# PROB_S7CAS_FPGA_1.net
KiCad netlist of a schematic drawn in Altium Designer
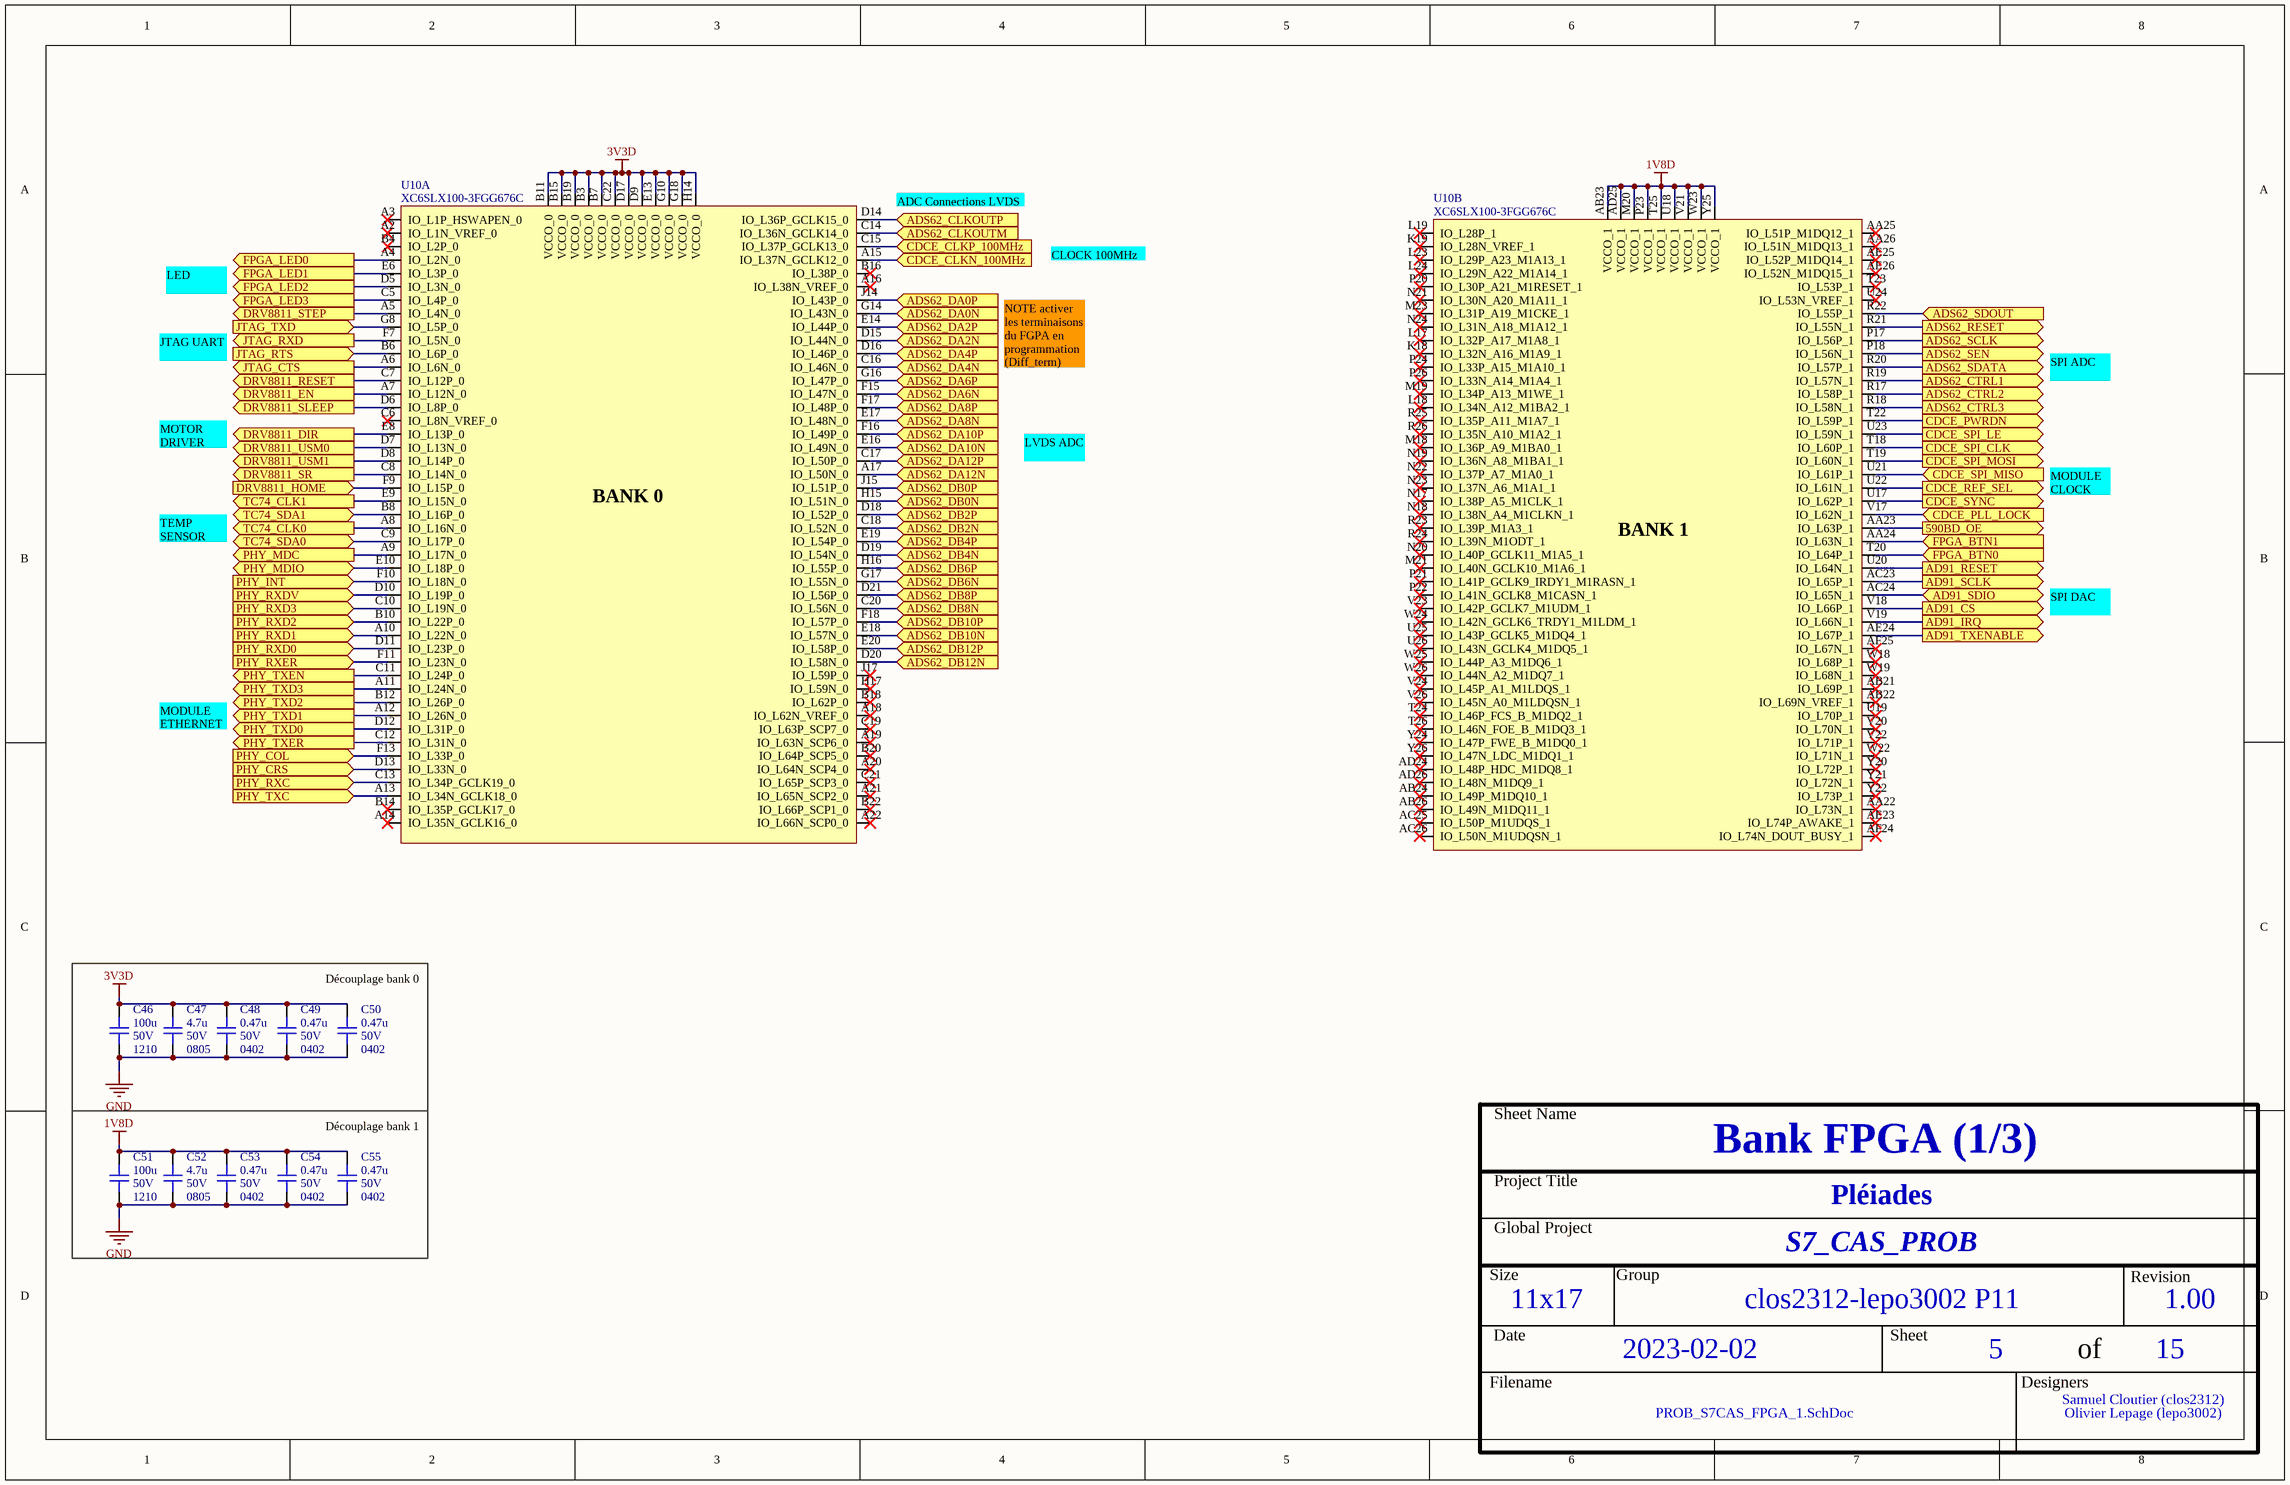
[diagram p0: PROB_S7CAS_FPGA_1.SchDoc]

(export (version "E")
  (design (tool "Eeschema 10.0.6"))
  (components
    (comp (ref "C46")
      (value "100u")
      (footprint "CAP_1210")
      (description "CAP - 1210")
      (fields
        (field (name "VOLTAGE") "50V")
        (field (name "PACKAGE") "1210")
        (field (name "CREATEDBY") "Jonathan Bouchard")
      )
      (libsource (lib "S7CAS_LIB2021") (part "CAP - 1210"))
    )
    (comp (ref "C47")
      (value "4.7u")
      (footprint "CAP_0805")
      (description "CAP - 0805")
      (fields
        (field (name "VOLTAGE") "50V")
        (field (name "PACKAGE") "0805")
        (field (name "CREATEDBY") "Jonathan Bouchard")
      )
      (libsource (lib "S7CAS_LIB2021") (part "CAP - 0805"))
    )
    (comp (ref "C48")
      (value "0.47u")
      (footprint "CAP_0402")
      (description "CAP - 0402")
      (fields
        (field (name "VOLTAGE") "50V")
        (field (name "PACKAGE") "0402")
        (field (name "CREATEDBY") "Jonathan Bouchard")
      )
      (libsource (lib "S7CAS_LIB2021") (part "CAP - 0402"))
    )
    (comp (ref "C49")
      (value "0.47u")
      (footprint "CAP_0402")
      (description "CAP - 0402")
      (fields
        (field (name "VOLTAGE") "50V")
        (field (name "PACKAGE") "0402")
        (field (name "CREATEDBY") "Jonathan Bouchard")
      )
      (libsource (lib "S7CAS_LIB2021") (part "CAP - 0402"))
    )
    (comp (ref "C50")
      (value "0.47u")
      (footprint "CAP_0402")
      (description "CAP - 0402")
      (fields
        (field (name "VOLTAGE") "50V")
        (field (name "PACKAGE") "0402")
        (field (name "CREATEDBY") "Jonathan Bouchard")
      )
      (libsource (lib "S7CAS_LIB2021") (part "CAP - 0402"))
    )
    (comp (ref "C51")
      (value "100u")
      (footprint "CAP_1210")
      (description "CAP - 1210")
      (fields
        (field (name "VOLTAGE") "50V")
        (field (name "PACKAGE") "1210")
        (field (name "CREATEDBY") "Jonathan Bouchard")
      )
      (libsource (lib "S7CAS_LIB2021") (part "CAP - 1210"))
    )
    (comp (ref "C52")
      (value "4.7u")
      (footprint "CAP_0805")
      (description "CAP - 0805")
      (fields
        (field (name "VOLTAGE") "50V")
        (field (name "PACKAGE") "0805")
        (field (name "CREATEDBY") "Jonathan Bouchard")
      )
      (libsource (lib "S7CAS_LIB2021") (part "CAP - 0805"))
    )
    (comp (ref "C53")
      (value "0.47u")
      (footprint "CAP_0402")
      (description "CAP - 0402")
      (fields
        (field (name "VOLTAGE") "50V")
        (field (name "PACKAGE") "0402")
        (field (name "CREATEDBY") "Jonathan Bouchard")
      )
      (libsource (lib "S7CAS_LIB2021") (part "CAP - 0402"))
    )
    (comp (ref "C54")
      (value "0.47u")
      (footprint "CAP_0402")
      (description "CAP - 0402")
      (fields
        (field (name "VOLTAGE") "50V")
        (field (name "PACKAGE") "0402")
        (field (name "CREATEDBY") "Jonathan Bouchard")
      )
      (libsource (lib "S7CAS_LIB2021") (part "CAP - 0402"))
    )
    (comp (ref "C55")
      (value "0.47u")
      (footprint "CAP_0402")
      (description "CAP - 0402")
      (fields
        (field (name "VOLTAGE") "50V")
        (field (name "PACKAGE") "0402")
        (field (name "CREATEDBY") "Jonathan Bouchard")
      )
      (libsource (lib "S7CAS_LIB2021") (part "CAP - 0402"))
    )
    (comp (ref "U10")
      (value "XC6SLX100-3FGG676C")
      (footprint "FPGA_XILINX_FGG676")
      (description "FPGA - XILINX SPARTAN 6 480 I/O - BGA-676")
      (fields
        (field (name "VOLTAGE") "1.14 V ~ 1.26 V")
        (field (name "MFG") "Xilinx")
        (field (name "CREATEDBY") "Jonathan Bouchard")
      )
      (libsource (lib "S7CAS_LIB2021") (part "FPGA_XC6SLX100-3FGG676C"))
    )
  )
  (nets
    (net (code "1") (name "/590BD_OE") (class "Default")
      (node (ref "U10") (pin "AA23") (pinfunction "IO_L63P_1_AA23") (pintype "passive"))
    )
    (net (code "2") (name "/AD91_CS") (class "Default")
      (node (ref "U10") (pin "V18") (pinfunction "IO_L66P_1_V18") (pintype "passive"))
    )
    (net (code "3") (name "/AD91_IRQ") (class "Default")
      (node (ref "U10") (pin "V19") (pinfunction "IO_L66N_1_V19") (pintype "passive"))
    )
    (net (code "4") (name "/AD91_RESET") (class "Default")
      (node (ref "U10") (pin "U20") (pinfunction "IO_L64N_1_U20") (pintype "passive"))
    )
    (net (code "5") (name "/AD91_SCLK") (class "Default")
      (node (ref "U10") (pin "AC23") (pinfunction "IO_L65P_1_AC23") (pintype "passive"))
    )
    (net (code "6") (name "/AD91_SDIO") (class "Default")
      (node (ref "U10") (pin "AC24") (pinfunction "IO_L65N_1_AC24") (pintype "passive"))
    )
    (net (code "7") (name "/AD91_TXENABLE") (class "Default")
      (node (ref "U10") (pin "AE24") (pinfunction "IO_L67P_1_AE24") (pintype "passive"))
    )
    (net (code "8") (name "/ADS62_CLKOUTM") (class "Default")
      (node (ref "U10") (pin "C14") (pinfunction "IO_L36N_GCLK14_0_C14") (pintype "passive"))
    )
    (net (code "9") (name "/ADS62_CLKOUTP") (class "Default")
      (node (ref "U10") (pin "D14") (pinfunction "IO_L36P_GCLK15_0_D14") (pintype "passive"))
    )
    (net (code "10") (name "/ADS62_CTRL1") (class "Default")
      (node (ref "U10") (pin "R19") (pinfunction "IO_L57N_1_R19") (pintype "passive"))
    )
    (net (code "11") (name "/ADS62_CTRL2") (class "Default")
      (node (ref "U10") (pin "R17") (pinfunction "IO_L58P_1_R17") (pintype "passive"))
    )
    (net (code "12") (name "/ADS62_CTRL3") (class "Default")
      (node (ref "U10") (pin "R18") (pinfunction "IO_L58N_1_R18") (pintype "passive"))
    )
    (net (code "13") (name "/ADS62_DA0N") (class "Default")
      (node (ref "U10") (pin "G14") (pinfunction "IO_L43N_0_G14") (pintype "passive"))
    )
    (net (code "14") (name "/ADS62_DA0P") (class "Default")
      (node (ref "U10") (pin "J14") (pinfunction "IO_L43P_0_J14") (pintype "passive"))
    )
    (net (code "15") (name "/ADS62_DA2N") (class "Default")
      (node (ref "U10") (pin "D15") (pinfunction "IO_L44N_0_D15") (pintype "passive"))
    )
    (net (code "16") (name "/ADS62_DA2P") (class "Default")
      (node (ref "U10") (pin "E14") (pinfunction "IO_L44P_0_E14") (pintype "passive"))
    )
    (net (code "17") (name "/ADS62_DA4N") (class "Default")
      (node (ref "U10") (pin "C16") (pinfunction "IO_L46N_0_C16") (pintype "passive"))
    )
    (net (code "18") (name "/ADS62_DA4P") (class "Default")
      (node (ref "U10") (pin "D16") (pinfunction "IO_L46P_0_D16") (pintype "passive"))
    )
    (net (code "19") (name "/ADS62_DA6N") (class "Default")
      (node (ref "U10") (pin "F15") (pinfunction "IO_L47N_0_F15") (pintype "passive"))
    )
    (net (code "20") (name "/ADS62_DA6P") (class "Default")
      (node (ref "U10") (pin "G16") (pinfunction "IO_L47P_0_G16") (pintype "passive"))
    )
    (net (code "21") (name "/ADS62_DA8N") (class "Default")
      (node (ref "U10") (pin "E17") (pinfunction "IO_L48N_0_E17") (pintype "passive"))
    )
    (net (code "22") (name "/ADS62_DA8P") (class "Default")
      (node (ref "U10") (pin "F17") (pinfunction "IO_L48P_0_F17") (pintype "passive"))
    )
    (net (code "23") (name "/ADS62_DA10N") (class "Default")
      (node (ref "U10") (pin "E16") (pinfunction "IO_L49N_0_E16") (pintype "passive"))
    )
    (net (code "24") (name "/ADS62_DA10P") (class "Default")
      (node (ref "U10") (pin "F16") (pinfunction "IO_L49P_0_F16") (pintype "passive"))
    )
    (net (code "25") (name "/ADS62_DA12N") (class "Default")
      (node (ref "U10") (pin "A17") (pinfunction "IO_L50N_0_A17") (pintype "passive"))
    )
    (net (code "26") (name "/ADS62_DA12P") (class "Default")
      (node (ref "U10") (pin "C17") (pinfunction "IO_L50P_0_C17") (pintype "passive"))
    )
    (net (code "27") (name "/ADS62_DB0N") (class "Default")
      (node (ref "U10") (pin "H15") (pinfunction "IO_L51N_0_H15") (pintype "passive"))
    )
    (net (code "28") (name "/ADS62_DB0P") (class "Default")
      (node (ref "U10") (pin "J15") (pinfunction "IO_L51P_0_J15") (pintype "passive"))
    )
    (net (code "29") (name "/ADS62_DB2N") (class "Default")
      (node (ref "U10") (pin "C18") (pinfunction "IO_L52N_0_C18") (pintype "passive"))
    )
    (net (code "30") (name "/ADS62_DB2P") (class "Default")
      (node (ref "U10") (pin "D18") (pinfunction "IO_L52P_0_D18") (pintype "passive"))
    )
    (net (code "31") (name "/ADS62_DB4N") (class "Default")
      (node (ref "U10") (pin "D19") (pinfunction "IO_L54N_0_D19") (pintype "passive"))
    )
    (net (code "32") (name "/ADS62_DB4P") (class "Default")
      (node (ref "U10") (pin "E19") (pinfunction "IO_L54P_0_E19") (pintype "passive"))
    )
    (net (code "33") (name "/ADS62_DB6N") (class "Default")
      (node (ref "U10") (pin "G17") (pinfunction "IO_L55N_0_G17") (pintype "passive"))
    )
    (net (code "34") (name "/ADS62_DB6P") (class "Default")
      (node (ref "U10") (pin "H16") (pinfunction "IO_L55P_0_H16") (pintype "passive"))
    )
    (net (code "35") (name "/ADS62_DB8N") (class "Default")
      (node (ref "U10") (pin "C20") (pinfunction "IO_L56N_0_C20") (pintype "passive"))
    )
    (net (code "36") (name "/ADS62_DB8P") (class "Default")
      (node (ref "U10") (pin "D21") (pinfunction "IO_L56P_0_D21") (pintype "passive"))
    )
    (net (code "37") (name "/ADS62_DB10N") (class "Default")
      (node (ref "U10") (pin "E18") (pinfunction "IO_L57N_0_E18") (pintype "passive"))
    )
    (net (code "38") (name "/ADS62_DB10P") (class "Default")
      (node (ref "U10") (pin "F18") (pinfunction "IO_L57P_0_F18") (pintype "passive"))
    )
    (net (code "39") (name "/ADS62_DB12N") (class "Default")
      (node (ref "U10") (pin "D20") (pinfunction "IO_L58N_0_D20") (pintype "passive"))
    )
    (net (code "40") (name "/ADS62_DB12P") (class "Default")
      (node (ref "U10") (pin "E20") (pinfunction "IO_L58P_0_E20") (pintype "passive"))
    )
    (net (code "41") (name "/ADS62_RESET") (class "Default")
      (node (ref "U10") (pin "R21") (pinfunction "IO_L55N_1_R21") (pintype "passive"))
    )
    (net (code "42") (name "/ADS62_SCLK") (class "Default")
      (node (ref "U10") (pin "P17") (pinfunction "IO_L56P_1_P17") (pintype "passive"))
    )
    (net (code "43") (name "/ADS62_SDATA") (class "Default")
      (node (ref "U10") (pin "R20") (pinfunction "IO_L57P_1_R20") (pintype "passive"))
    )
    (net (code "44") (name "/ADS62_SDOUT") (class "Default")
      (node (ref "U10") (pin "R22") (pinfunction "IO_L55P_1_R22") (pintype "passive"))
    )
    (net (code "45") (name "/ADS62_SEN") (class "Default")
      (node (ref "U10") (pin "P18") (pinfunction "IO_L56N_1_P18") (pintype "passive"))
    )
    (net (code "46") (name "/CDCE_CLKN_100MHz") (class "Default")
      (node (ref "U10") (pin "A15") (pinfunction "IO_L37N_GCLK12_0_A15") (pintype "passive"))
    )
    (net (code "47") (name "/CDCE_CLKP_100MHz") (class "Default")
      (node (ref "U10") (pin "C15") (pinfunction "IO_L37P_GCLK13_0_C15") (pintype "passive"))
    )
    (net (code "48") (name "/CDCE_PLL_LOCK") (class "Default")
      (node (ref "U10") (pin "V17") (pinfunction "IO_L62N_1_V17") (pintype "passive"))
    )
    (net (code "49") (name "/CDCE_PWRDN") (class "Default")
      (node (ref "U10") (pin "T22") (pinfunction "IO_L59P_1_T22") (pintype "passive"))
    )
    (net (code "50") (name "/CDCE_REF_SEL") (class "Default")
      (node (ref "U10") (pin "U22") (pinfunction "IO_L61N_1_U22") (pintype "passive"))
    )
    (net (code "51") (name "/CDCE_SPI_CLK") (class "Default")
      (node (ref "U10") (pin "T18") (pinfunction "IO_L60P_1_T18") (pintype "passive"))
    )
    (net (code "52") (name "/CDCE_SPI_LE") (class "Default")
      (node (ref "U10") (pin "U23") (pinfunction "IO_L59N_1_U23") (pintype "passive"))
    )
    (net (code "53") (name "/CDCE_SPI_MISO") (class "Default")
      (node (ref "U10") (pin "U21") (pinfunction "IO_L61P_1_U21") (pintype "passive"))
    )
    (net (code "54") (name "/CDCE_SPI_MOSI") (class "Default")
      (node (ref "U10") (pin "T19") (pinfunction "IO_L60N_1_T19") (pintype "passive"))
    )
    (net (code "55") (name "/CDCE_SYNC") (class "Default")
      (node (ref "U10") (pin "U17") (pinfunction "IO_L62P_1_U17") (pintype "passive"))
    )
    (net (code "56") (name "/DRV8811_DIR") (class "Default")
      (node (ref "U10") (pin "E8") (pinfunction "IO_L13P_0_E8") (pintype "passive"))
    )
    (net (code "57") (name "/DRV8811_EN") (class "Default")
      (node (ref "U10") (pin "A7") (pinfunction "IO_L12N_0_A7") (pintype "passive"))
    )
    (net (code "58") (name "/DRV8811_HOME") (class "Default")
      (node (ref "U10") (pin "F9") (pinfunction "IO_L15P_0_F9") (pintype "passive"))
    )
    (net (code "59") (name "/DRV8811_RESET") (class "Default")
      (node (ref "U10") (pin "C7") (pinfunction "IO_L12P_0_C7") (pintype "passive"))
    )
    (net (code "60") (name "/DRV8811_SLEEP") (class "Default")
      (node (ref "U10") (pin "D6") (pinfunction "IO_L8P_0_D6") (pintype "passive"))
    )
    (net (code "61") (name "/DRV8811_SR") (class "Default")
      (node (ref "U10") (pin "C8") (pinfunction "IO_L14N_0_C8") (pintype "passive"))
    )
    (net (code "62") (name "/DRV8811_STEP") (class "Default")
      (node (ref "U10") (pin "A5") (pinfunction "IO_L4N_0_A5") (pintype "passive"))
    )
    (net (code "63") (name "/DRV8811_USM0") (class "Default")
      (node (ref "U10") (pin "D7") (pinfunction "IO_L13N_0_D7") (pintype "passive"))
    )
    (net (code "64") (name "/DRV8811_USM1") (class "Default")
      (node (ref "U10") (pin "D8") (pinfunction "IO_L14P_0_D8") (pintype "passive"))
    )
    (net (code "65") (name "/FPGA_BTN0") (class "Default")
      (node (ref "U10") (pin "T20") (pinfunction "IO_L64P_1_T20") (pintype "passive"))
    )
    (net (code "66") (name "/FPGA_BTN1") (class "Default")
      (node (ref "U10") (pin "AA24") (pinfunction "IO_L63N_1_AA24") (pintype "passive"))
    )
    (net (code "67") (name "/FPGA_LED0") (class "Default")
      (node (ref "U10") (pin "A4") (pinfunction "IO_L2N_0_A4") (pintype "passive"))
    )
    (net (code "68") (name "/FPGA_LED1") (class "Default")
      (node (ref "U10") (pin "E6") (pinfunction "IO_L3P_0_E6") (pintype "passive"))
    )
    (net (code "69") (name "/FPGA_LED2") (class "Default")
      (node (ref "U10") (pin "D5") (pinfunction "IO_L3N_0_D5") (pintype "passive"))
    )
    (net (code "70") (name "/FPGA_LED3") (class "Default")
      (node (ref "U10") (pin "C5") (pinfunction "IO_L4P_0_C5") (pintype "passive"))
    )
    (net (code "71") (name "/JTAG_CTS") (class "Default")
      (node (ref "U10") (pin "A6") (pinfunction "IO_L6N_0_A6") (pintype "passive"))
    )
    (net (code "72") (name "/JTAG_RTS") (class "Default")
      (node (ref "U10") (pin "B6") (pinfunction "IO_L6P_0_B6") (pintype "passive"))
    )
    (net (code "73") (name "/JTAG_RXD") (class "Default")
      (node (ref "U10") (pin "F7") (pinfunction "IO_L5N_0_F7") (pintype "passive"))
    )
    (net (code "74") (name "/JTAG_TXD") (class "Default")
      (node (ref "U10") (pin "G8") (pinfunction "IO_L5P_0_G8") (pintype "passive"))
    )
    (net (code "75") (name "/PHY_COL") (class "Default")
      (node (ref "U10") (pin "F13") (pinfunction "IO_L33P_0_F13") (pintype "passive"))
    )
    (net (code "76") (name "/PHY_CRS") (class "Default")
      (node (ref "U10") (pin "D13") (pinfunction "IO_L33N_0_D13") (pintype "passive"))
    )
    (net (code "77") (name "/PHY_INT") (class "Default")
      (node (ref "U10") (pin "F10") (pinfunction "IO_L18N_0_F10") (pintype "passive"))
    )
    (net (code "78") (name "/PHY_MDC") (class "Default")
      (node (ref "U10") (pin "A9") (pinfunction "IO_L17N_0_A9") (pintype "passive"))
    )
    (net (code "79") (name "/PHY_MDIO") (class "Default")
      (node (ref "U10") (pin "E10") (pinfunction "IO_L18P_0_E10") (pintype "passive"))
    )
    (net (code "80") (name "/PHY_RXC") (class "Default")
      (node (ref "U10") (pin "C13") (pinfunction "IO_L34P_GCLK19_0_C13") (pintype "passive"))
    )
    (net (code "81") (name "/PHY_RXD0") (class "Default")
      (node (ref "U10") (pin "D11") (pinfunction "IO_L23P_0_D11") (pintype "passive"))
    )
    (net (code "82") (name "/PHY_RXD1") (class "Default")
      (node (ref "U10") (pin "A10") (pinfunction "IO_L22N_0_A10") (pintype "passive"))
    )
    (net (code "83") (name "/PHY_RXD2") (class "Default")
      (node (ref "U10") (pin "B10") (pinfunction "IO_L22P_0_B10") (pintype "passive"))
    )
    (net (code "84") (name "/PHY_RXD3") (class "Default")
      (node (ref "U10") (pin "C10") (pinfunction "IO_L19N_0_C10") (pintype "passive"))
    )
    (net (code "85") (name "/PHY_RXDV") (class "Default")
      (node (ref "U10") (pin "D10") (pinfunction "IO_L19P_0_D10") (pintype "passive"))
    )
    (net (code "86") (name "/PHY_RXER") (class "Default")
      (node (ref "U10") (pin "F11") (pinfunction "IO_L23N_0_F11") (pintype "passive"))
    )
    (net (code "87") (name "/PHY_TXC") (class "Default")
      (node (ref "U10") (pin "A13") (pinfunction "IO_L34N_GCLK18_0_A13") (pintype "passive"))
    )
    (net (code "88") (name "/PHY_TXD0") (class "Default")
      (node (ref "U10") (pin "D12") (pinfunction "IO_L31P_0_D12") (pintype "passive"))
    )
    (net (code "89") (name "/PHY_TXD1") (class "Default")
      (node (ref "U10") (pin "A12") (pinfunction "IO_L26N_0_A12") (pintype "passive"))
    )
    (net (code "90") (name "/PHY_TXD2") (class "Default")
      (node (ref "U10") (pin "B12") (pinfunction "IO_L26P_0_B12") (pintype "passive"))
    )
    (net (code "91") (name "/PHY_TXD3") (class "Default")
      (node (ref "U10") (pin "A11") (pinfunction "IO_L24N_0_A11") (pintype "passive"))
    )
    (net (code "92") (name "/PHY_TXEN") (class "Default")
      (node (ref "U10") (pin "C11") (pinfunction "IO_L24P_0_C11") (pintype "passive"))
    )
    (net (code "93") (name "/PHY_TXER") (class "Default")
      (node (ref "U10") (pin "C12") (pinfunction "IO_L31N_0_C12") (pintype "passive"))
    )
    (net (code "94") (name "/TC74_CLK0") (class "Default")
      (node (ref "U10") (pin "A8") (pinfunction "IO_L16N_0_A8") (pintype "passive"))
    )
    (net (code "95") (name "/TC74_CLK1") (class "Default")
      (node (ref "U10") (pin "E9") (pinfunction "IO_L15N_0_E9") (pintype "passive"))
    )
    (net (code "96") (name "/TC74_SDA0") (class "Default")
      (node (ref "U10") (pin "C9") (pinfunction "IO_L17P_0_C9") (pintype "passive"))
    )
    (net (code "97") (name "/TC74_SDA1") (class "Default")
      (node (ref "U10") (pin "B8") (pinfunction "IO_L16P_0_B8") (pintype "passive"))
    )
    (net (code "98") (name "1V8D") (class "Default")
      (node (ref "C51") (pin "2") (pinfunction "2_2") (pintype "passive"))
      (node (ref "C52") (pin "2") (pinfunction "2_2") (pintype "passive"))
      (node (ref "C53") (pin "2") (pinfunction "2_2") (pintype "passive"))
      (node (ref "C54") (pin "2") (pinfunction "2_2") (pintype "passive"))
      (node (ref "C55") (pin "2") (pinfunction "2_2") (pintype "passive"))
      (node (ref "U10") (pin "AB23") (pinfunction "VCCO_1_AB23") (pintype "passive"))
      (node (ref "U10") (pin "AD25") (pinfunction "VCCO_1_AD25") (pintype "passive"))
      (node (ref "U10") (pin "M20") (pinfunction "VCCO_1_M20") (pintype "passive"))
      (node (ref "U10") (pin "P23") (pinfunction "VCCO_1_P23") (pintype "passive"))
      (node (ref "U10") (pin "T25") (pinfunction "VCCO_1_T25") (pintype "passive"))
      (node (ref "U10") (pin "U18") (pinfunction "VCCO_1_U18") (pintype "passive"))
      (node (ref "U10") (pin "V21") (pinfunction "VCCO_1_V21") (pintype "passive"))
      (node (ref "U10") (pin "W23") (pinfunction "VCCO_1_W23") (pintype "passive"))
      (node (ref "U10") (pin "Y25") (pinfunction "VCCO_1_Y25") (pintype "passive"))
    )
    (net (code "99") (name "3V3D") (class "Default")
      (node (ref "C46") (pin "2") (pinfunction "2_2") (pintype "passive"))
      (node (ref "C47") (pin "2") (pinfunction "2_2") (pintype "passive"))
      (node (ref "C48") (pin "2") (pinfunction "2_2") (pintype "passive"))
      (node (ref "C49") (pin "2") (pinfunction "2_2") (pintype "passive"))
      (node (ref "C50") (pin "2") (pinfunction "2_2") (pintype "passive"))
      (node (ref "U10") (pin "B11") (pinfunction "VCCO_0_B11") (pintype "passive"))
      (node (ref "U10") (pin "B15") (pinfunction "VCCO_0_B15") (pintype "passive"))
      (node (ref "U10") (pin "B19") (pinfunction "VCCO_0_B19") (pintype "passive"))
      (node (ref "U10") (pin "B3") (pinfunction "VCCO_0_B3") (pintype "passive"))
      (node (ref "U10") (pin "B7") (pinfunction "VCCO_0_B7") (pintype "passive"))
      (node (ref "U10") (pin "C22") (pinfunction "VCCO_0_C22") (pintype "passive"))
      (node (ref "U10") (pin "D17") (pinfunction "VCCO_0_D17") (pintype "passive"))
      (node (ref "U10") (pin "D9") (pinfunction "VCCO_0_D9") (pintype "passive"))
      (node (ref "U10") (pin "E13") (pinfunction "VCCO_0_E13") (pintype "passive"))
      (node (ref "U10") (pin "G10") (pinfunction "VCCO_0_G10") (pintype "passive"))
      (node (ref "U10") (pin "G18") (pinfunction "VCCO_0_G18") (pintype "passive"))
      (node (ref "U10") (pin "H14") (pinfunction "VCCO_0_H14") (pintype "passive"))
    )
    (net (code "100") (name "GND") (class "Default")
      (node (ref "C46") (pin "1") (pinfunction "1_1") (pintype "passive"))
      (node (ref "C47") (pin "1") (pinfunction "1_1") (pintype "passive"))
      (node (ref "C48") (pin "1") (pinfunction "1_1") (pintype "passive"))
      (node (ref "C49") (pin "1") (pinfunction "1_1") (pintype "passive"))
      (node (ref "C50") (pin "1") (pinfunction "1_1") (pintype "passive"))
      (node (ref "C51") (pin "1") (pinfunction "1_1") (pintype "passive"))
      (node (ref "C52") (pin "1") (pinfunction "1_1") (pintype "passive"))
      (node (ref "C53") (pin "1") (pinfunction "1_1") (pintype "passive"))
      (node (ref "C54") (pin "1") (pinfunction "1_1") (pintype "passive"))
      (node (ref "C55") (pin "1") (pinfunction "1_1") (pintype "passive"))
    )
    (net (code "101") (name "unconnected-(U10A-IO_L1N_VREF_0-PadA2)") (class "Default")
      (node (ref "U10") (pin "A2") (pinfunction "IO_L1N_VREF_0_A2") (pintype "passive+no_connect"))
    )
    (net (code "102") (name "unconnected-(U10A-IO_L1P_HSWAPEN_0-PadA3)") (class "Default")
      (node (ref "U10") (pin "A3") (pinfunction "IO_L1P_HSWAPEN_0_A3") (pintype "passive+no_connect"))
    )
    (net (code "103") (name "unconnected-(U10A-IO_L2P_0-PadB4)") (class "Default")
      (node (ref "U10") (pin "B4") (pinfunction "IO_L2P_0_B4") (pintype "passive+no_connect"))
    )
    (net (code "104") (name "unconnected-(U10A-IO_L8N_VREF_0-PadC6)") (class "Default")
      (node (ref "U10") (pin "C6") (pinfunction "IO_L8N_VREF_0_C6") (pintype "passive+no_connect"))
    )
    (net (code "105") (name "unconnected-(U10A-IO_L35N_GCLK16_0-PadA14)") (class "Default")
      (node (ref "U10") (pin "A14") (pinfunction "IO_L35N_GCLK16_0_A14") (pintype "passive+no_connect"))
    )
    (net (code "106") (name "unconnected-(U10A-IO_L35P_GCLK17_0-PadB14)") (class "Default")
      (node (ref "U10") (pin "B14") (pinfunction "IO_L35P_GCLK17_0_B14") (pintype "passive+no_connect"))
    )
    (net (code "107") (name "unconnected-(U10A-IO_L38N_VREF_0-PadA16)") (class "Default")
      (node (ref "U10") (pin "A16") (pinfunction "IO_L38N_VREF_0_A16") (pintype "passive+no_connect"))
    )
    (net (code "108") (name "unconnected-(U10A-IO_L38P_0-PadB16)") (class "Default")
      (node (ref "U10") (pin "B16") (pinfunction "IO_L38P_0_B16") (pintype "passive+no_connect"))
    )
    (net (code "109") (name "unconnected-(U10A-IO_L59N_0-PadH17)") (class "Default")
      (node (ref "U10") (pin "H17") (pinfunction "IO_L59N_0_H17") (pintype "passive+no_connect"))
    )
    (net (code "110") (name "unconnected-(U10A-IO_L59P_0-PadJ17)") (class "Default")
      (node (ref "U10") (pin "J17") (pinfunction "IO_L59P_0_J17") (pintype "passive+no_connect"))
    )
    (net (code "111") (name "unconnected-(U10A-IO_L62N_VREF_0-PadA18)") (class "Default")
      (node (ref "U10") (pin "A18") (pinfunction "IO_L62N_VREF_0_A18") (pintype "passive+no_connect"))
    )
    (net (code "112") (name "unconnected-(U10A-IO_L62P_0-PadB18)") (class "Default")
      (node (ref "U10") (pin "B18") (pinfunction "IO_L62P_0_B18") (pintype "passive+no_connect"))
    )
    (net (code "113") (name "unconnected-(U10A-IO_L63N_SCP6_0-PadA19)") (class "Default")
      (node (ref "U10") (pin "A19") (pinfunction "IO_L63N_SCP6_0_A19") (pintype "passive+no_connect"))
    )
    (net (code "114") (name "unconnected-(U10A-IO_L63P_SCP7_0-PadC19)") (class "Default")
      (node (ref "U10") (pin "C19") (pinfunction "IO_L63P_SCP7_0_C19") (pintype "passive+no_connect"))
    )
    (net (code "115") (name "unconnected-(U10A-IO_L64N_SCP4_0-PadA20)") (class "Default")
      (node (ref "U10") (pin "A20") (pinfunction "IO_L64N_SCP4_0_A20") (pintype "passive+no_connect"))
    )
    (net (code "116") (name "unconnected-(U10A-IO_L64P_SCP5_0-PadB20)") (class "Default")
      (node (ref "U10") (pin "B20") (pinfunction "IO_L64P_SCP5_0_B20") (pintype "passive+no_connect"))
    )
    (net (code "117") (name "unconnected-(U10A-IO_L65N_SCP2_0-PadA21)") (class "Default")
      (node (ref "U10") (pin "A21") (pinfunction "IO_L65N_SCP2_0_A21") (pintype "passive+no_connect"))
    )
    (net (code "118") (name "unconnected-(U10A-IO_L65P_SCP3_0-PadC21)") (class "Default")
      (node (ref "U10") (pin "C21") (pinfunction "IO_L65P_SCP3_0_C21") (pintype "passive+no_connect"))
    )
    (net (code "119") (name "unconnected-(U10A-IO_L66N_SCP0_0-PadA22)") (class "Default")
      (node (ref "U10") (pin "A22") (pinfunction "IO_L66N_SCP0_0_A22") (pintype "passive+no_connect"))
    )
    (net (code "120") (name "unconnected-(U10A-IO_L66P_SCP1_0-PadB22)") (class "Default")
      (node (ref "U10") (pin "B22") (pinfunction "IO_L66P_SCP1_0_B22") (pintype "passive+no_connect"))
    )
    (net (code "121") (name "unconnected-(U10B-IO_L28N_VREF_1-PadK19)") (class "Default")
      (node (ref "U10") (pin "K19") (pinfunction "IO_L28N_VREF_1_K19") (pintype "passive+no_connect"))
    )
    (net (code "122") (name "unconnected-(U10B-IO_L28P_1-PadL19)") (class "Default")
      (node (ref "U10") (pin "L19") (pinfunction "IO_L28P_1_L19") (pintype "passive+no_connect"))
    )
    (net (code "123") (name "unconnected-(U10B-IO_L29N_A22_M1A14_1-PadL24)") (class "Default")
      (node (ref "U10") (pin "L24") (pinfunction "IO_L29N_A22_M1A14_1_L24") (pintype "passive+no_connect"))
    )
    (net (code "124") (name "unconnected-(U10B-IO_L29P_A23_M1A13_1-PadL23)") (class "Default")
      (node (ref "U10") (pin "L23") (pinfunction "IO_L29P_A23_M1A13_1_L23") (pintype "passive+no_connect"))
    )
    (net (code "125") (name "unconnected-(U10B-IO_L30N_A20_M1A11_1-PadN21)") (class "Default")
      (node (ref "U10") (pin "N21") (pinfunction "IO_L30N_A20_M1A11_1_N21") (pintype "passive+no_connect"))
    )
    (net (code "126") (name "unconnected-(U10B-IO_L30P_A21_M1RESET_1-PadP20)") (class "Default")
      (node (ref "U10") (pin "P20") (pinfunction "IO_L30P_A21_M1RESET_1_P20") (pintype "passive+no_connect"))
    )
    (net (code "127") (name "unconnected-(U10B-IO_L31N_A18_M1A12_1-PadN24)") (class "Default")
      (node (ref "U10") (pin "N24") (pinfunction "IO_L31N_A18_M1A12_1_N24") (pintype "passive+no_connect"))
    )
    (net (code "128") (name "unconnected-(U10B-IO_L31P_A19_M1CKE_1-PadM23)") (class "Default")
      (node (ref "U10") (pin "M23") (pinfunction "IO_L31P_A19_M1CKE_1_M23") (pintype "passive+no_connect"))
    )
    (net (code "129") (name "unconnected-(U10B-IO_L32N_A16_M1A9_1-PadK18)") (class "Default")
      (node (ref "U10") (pin "K18") (pinfunction "IO_L32N_A16_M1A9_1_K18") (pintype "passive+no_connect"))
    )
    (net (code "130") (name "unconnected-(U10B-IO_L32P_A17_M1A8_1-PadL17)") (class "Default")
      (node (ref "U10") (pin "L17") (pinfunction "IO_L32P_A17_M1A8_1_L17") (pintype "passive+no_connect"))
    )
    (net (code "131") (name "unconnected-(U10B-IO_L33N_A14_M1A4_1-PadP26)") (class "Default")
      (node (ref "U10") (pin "P26") (pinfunction "IO_L33N_A14_M1A4_1_P26") (pintype "passive+no_connect"))
    )
    (net (code "132") (name "unconnected-(U10B-IO_L33P_A15_M1A10_1-PadP24)") (class "Default")
      (node (ref "U10") (pin "P24") (pinfunction "IO_L33P_A15_M1A10_1_P24") (pintype "passive+no_connect"))
    )
    (net (code "133") (name "unconnected-(U10B-IO_L34N_A12_M1BA2_1-PadL18)") (class "Default")
      (node (ref "U10") (pin "L18") (pinfunction "IO_L34N_A12_M1BA2_1_L18") (pintype "passive+no_connect"))
    )
    (net (code "134") (name "unconnected-(U10B-IO_L34P_A13_M1WE_1-PadM19)") (class "Default")
      (node (ref "U10") (pin "M19") (pinfunction "IO_L34P_A13_M1WE_1_M19") (pintype "passive+no_connect"))
    )
    (net (code "135") (name "unconnected-(U10B-IO_L35N_A10_M1A2_1-PadR26)") (class "Default")
      (node (ref "U10") (pin "R26") (pinfunction "IO_L35N_A10_M1A2_1_R26") (pintype "passive+no_connect"))
    )
    (net (code "136") (name "unconnected-(U10B-IO_L35P_A11_M1A7_1-PadR25)") (class "Default")
      (node (ref "U10") (pin "R25") (pinfunction "IO_L35P_A11_M1A7_1_R25") (pintype "passive+no_connect"))
    )
    (net (code "137") (name "unconnected-(U10B-IO_L36N_A8_M1BA1_1-PadN19)") (class "Default")
      (node (ref "U10") (pin "N19") (pinfunction "IO_L36N_A8_M1BA1_1_N19") (pintype "passive+no_connect"))
    )
    (net (code "138") (name "unconnected-(U10B-IO_L36P_A9_M1BA0_1-PadM18)") (class "Default")
      (node (ref "U10") (pin "M18") (pinfunction "IO_L36P_A9_M1BA0_1_M18") (pintype "passive+no_connect"))
    )
    (net (code "139") (name "unconnected-(U10B-IO_L37N_A6_M1A1_1-PadN23)") (class "Default")
      (node (ref "U10") (pin "N23") (pinfunction "IO_L37N_A6_M1A1_1_N23") (pintype "passive+no_connect"))
    )
    (net (code "140") (name "unconnected-(U10B-IO_L37P_A7_M1A0_1-PadN22)") (class "Default")
      (node (ref "U10") (pin "N22") (pinfunction "IO_L37P_A7_M1A0_1_N22") (pintype "passive+no_connect"))
    )
    (net (code "141") (name "unconnected-(U10B-IO_L38N_A4_M1CLKN_1-PadN18)") (class "Default")
      (node (ref "U10") (pin "N18") (pinfunction "IO_L38N_A4_M1CLKN_1_N18") (pintype "passive+no_connect"))
    )
    (net (code "142") (name "unconnected-(U10B-IO_L38P_A5_M1CLK_1-PadN17)") (class "Default")
      (node (ref "U10") (pin "N17") (pinfunction "IO_L38P_A5_M1CLK_1_N17") (pintype "passive+no_connect"))
    )
    (net (code "143") (name "unconnected-(U10B-IO_L39N_M1ODT_1-PadR24)") (class "Default")
      (node (ref "U10") (pin "R24") (pinfunction "IO_L39N_M1ODT_1_R24") (pintype "passive+no_connect"))
    )
    (net (code "144") (name "unconnected-(U10B-IO_L39P_M1A3_1-PadR23)") (class "Default")
      (node (ref "U10") (pin "R23") (pinfunction "IO_L39P_M1A3_1_R23") (pintype "passive+no_connect"))
    )
    (net (code "145") (name "unconnected-(U10B-IO_L40N_GCLK10_M1A6_1-PadM21)") (class "Default")
      (node (ref "U10") (pin "M21") (pinfunction "IO_L40N_GCLK10_M1A6_1_M21") (pintype "passive+no_connect"))
    )
    (net (code "146") (name "unconnected-(U10B-IO_L40P_GCLK11_M1A5_1-PadN20)") (class "Default")
      (node (ref "U10") (pin "N20") (pinfunction "IO_L40P_GCLK11_M1A5_1_N20") (pintype "passive+no_connect"))
    )
    (net (code "147") (name "unconnected-(U10B-IO_L41N_GCLK8_M1CASN_1-PadP22)") (class "Default")
      (node (ref "U10") (pin "P22") (pinfunction "IO_L41N_GCLK8_M1CASN_1_P22") (pintype "passive+no_connect"))
    )
    (net (code "148") (name "unconnected-(U10B-IO_L41P_GCLK9_IRDY1_M1RASN_1-PadP21)") (class "Default")
      (node (ref "U10") (pin "P21") (pinfunction "IO_L41P_GCLK9_IRDY1_M1RASN_1_P21") (pintype "passive+no_connect"))
    )
    (net (code "149") (name "unconnected-(U10B-IO_L42N_GCLK6_TRDY1_M1LDM_1-PadW24)") (class "Default")
      (node (ref "U10") (pin "W24") (pinfunction "IO_L42N_GCLK6_TRDY1_M1LDM_1_W24") (pintype "passive+no_connect"))
    )
    (net (code "150") (name "unconnected-(U10B-IO_L42P_GCLK7_M1UDM_1-PadV23)") (class "Default")
      (node (ref "U10") (pin "V23") (pinfunction "IO_L42P_GCLK7_M1UDM_1_V23") (pintype "passive+no_connect"))
    )
    (net (code "151") (name "unconnected-(U10B-IO_L43N_GCLK4_M1DQ5_1-PadU26)") (class "Default")
      (node (ref "U10") (pin "U26") (pinfunction "IO_L43N_GCLK4_M1DQ5_1_U26") (pintype "passive+no_connect"))
    )
    (net (code "152") (name "unconnected-(U10B-IO_L43P_GCLK5_M1DQ4_1-PadU25)") (class "Default")
      (node (ref "U10") (pin "U25") (pinfunction "IO_L43P_GCLK5_M1DQ4_1_U25") (pintype "passive+no_connect"))
    )
    (net (code "153") (name "unconnected-(U10B-IO_L44N_A2_M1DQ7_1-PadW26)") (class "Default")
      (node (ref "U10") (pin "W26") (pinfunction "IO_L44N_A2_M1DQ7_1_W26") (pintype "passive+no_connect"))
    )
    (net (code "154") (name "unconnected-(U10B-IO_L44P_A3_M1DQ6_1-PadW25)") (class "Default")
      (node (ref "U10") (pin "W25") (pinfunction "IO_L44P_A3_M1DQ6_1_W25") (pintype "passive+no_connect"))
    )
    (net (code "155") (name "unconnected-(U10B-IO_L45N_A0_M1LDQSN_1-PadV26)") (class "Default")
      (node (ref "U10") (pin "V26") (pinfunction "IO_L45N_A0_M1LDQSN_1_V26") (pintype "passive+no_connect"))
    )
    (net (code "156") (name "unconnected-(U10B-IO_L45P_A1_M1LDQS_1-PadV24)") (class "Default")
      (node (ref "U10") (pin "V24") (pinfunction "IO_L45P_A1_M1LDQS_1_V24") (pintype "passive+no_connect"))
    )
    (net (code "157") (name "unconnected-(U10B-IO_L46N_FOE_B_M1DQ3_1-PadT26)") (class "Default")
      (node (ref "U10") (pin "T26") (pinfunction "IO_L46N_FOE_B_M1DQ3_1_T26") (pintype "passive+no_connect"))
    )
    (net (code "158") (name "unconnected-(U10B-IO_L46P_FCS_B_M1DQ2_1-PadT24)") (class "Default")
      (node (ref "U10") (pin "T24") (pinfunction "IO_L46P_FCS_B_M1DQ2_1_T24") (pintype "passive+no_connect"))
    )
    (net (code "159") (name "unconnected-(U10B-IO_L47N_LDC_M1DQ1_1-PadY26)") (class "Default")
      (node (ref "U10") (pin "Y26") (pinfunction "IO_L47N_LDC_M1DQ1_1_Y26") (pintype "passive+no_connect"))
    )
    (net (code "160") (name "unconnected-(U10B-IO_L47P_FWE_B_M1DQ0_1-PadY24)") (class "Default")
      (node (ref "U10") (pin "Y24") (pinfunction "IO_L47P_FWE_B_M1DQ0_1_Y24") (pintype "passive+no_connect"))
    )
    (net (code "161") (name "unconnected-(U10B-IO_L48N_M1DQ9_1-PadAD26)") (class "Default")
      (node (ref "U10") (pin "AD26") (pinfunction "IO_L48N_M1DQ9_1_AD26") (pintype "passive+no_connect"))
    )
    (net (code "162") (name "unconnected-(U10B-IO_L48P_HDC_M1DQ8_1-PadAD24)") (class "Default")
      (node (ref "U10") (pin "AD24") (pinfunction "IO_L48P_HDC_M1DQ8_1_AD24") (pintype "passive+no_connect"))
    )
    (net (code "163") (name "unconnected-(U10B-IO_L49N_M1DQ11_1-PadAB26)") (class "Default")
      (node (ref "U10") (pin "AB26") (pinfunction "IO_L49N_M1DQ11_1_AB26") (pintype "passive+no_connect"))
    )
    (net (code "164") (name "unconnected-(U10B-IO_L49P_M1DQ10_1-PadAB24)") (class "Default")
      (node (ref "U10") (pin "AB24") (pinfunction "IO_L49P_M1DQ10_1_AB24") (pintype "passive+no_connect"))
    )
    (net (code "165") (name "unconnected-(U10B-IO_L50N_M1UDQSN_1-PadAC26)") (class "Default")
      (node (ref "U10") (pin "AC26") (pinfunction "IO_L50N_M1UDQSN_1_AC26") (pintype "passive+no_connect"))
    )
    (net (code "166") (name "unconnected-(U10B-IO_L50P_M1UDQS_1-PadAC25)") (class "Default")
      (node (ref "U10") (pin "AC25") (pinfunction "IO_L50P_M1UDQS_1_AC25") (pintype "passive+no_connect"))
    )
    (net (code "167") (name "unconnected-(U10B-IO_L51N_M1DQ13_1-PadAA26)") (class "Default")
      (node (ref "U10") (pin "AA26") (pinfunction "IO_L51N_M1DQ13_1_AA26") (pintype "passive+no_connect"))
    )
    (net (code "168") (name "unconnected-(U10B-IO_L51P_M1DQ12_1-PadAA25)") (class "Default")
      (node (ref "U10") (pin "AA25") (pinfunction "IO_L51P_M1DQ12_1_AA25") (pintype "passive+no_connect"))
    )
    (net (code "169") (name "unconnected-(U10B-IO_L52N_M1DQ15_1-PadAE26)") (class "Default")
      (node (ref "U10") (pin "AE26") (pinfunction "IO_L52N_M1DQ15_1_AE26") (pintype "passive+no_connect"))
    )
    (net (code "170") (name "unconnected-(U10B-IO_L52P_M1DQ14_1-PadAE25)") (class "Default")
      (node (ref "U10") (pin "AE25") (pinfunction "IO_L52P_M1DQ14_1_AE25") (pintype "passive+no_connect"))
    )
    (net (code "171") (name "unconnected-(U10B-IO_L53N_VREF_1-PadU24)") (class "Default")
      (node (ref "U10") (pin "U24") (pinfunction "IO_L53N_VREF_1_U24") (pintype "passive+no_connect"))
    )
    (net (code "172") (name "unconnected-(U10B-IO_L53P_1-PadT23)") (class "Default")
      (node (ref "U10") (pin "T23") (pinfunction "IO_L53P_1_T23") (pintype "passive+no_connect"))
    )
    (net (code "173") (name "unconnected-(U10B-IO_L67N_1-PadAF25)") (class "Default")
      (node (ref "U10") (pin "AF25") (pinfunction "IO_L67N_1_AF25") (pintype "passive+no_connect"))
    )
    (net (code "174") (name "unconnected-(U10B-IO_L68N_1-PadW19)") (class "Default")
      (node (ref "U10") (pin "W19") (pinfunction "IO_L68N_1_W19") (pintype "passive+no_connect"))
    )
    (net (code "175") (name "unconnected-(U10B-IO_L68P_1-PadW18)") (class "Default")
      (node (ref "U10") (pin "W18") (pinfunction "IO_L68P_1_W18") (pintype "passive+no_connect"))
    )
    (net (code "176") (name "unconnected-(U10B-IO_L69N_VREF_1-PadAB22)") (class "Default")
      (node (ref "U10") (pin "AB22") (pinfunction "IO_L69N_VREF_1_AB22") (pintype "passive+no_connect"))
    )
    (net (code "177") (name "unconnected-(U10B-IO_L69P_1-PadAB21)") (class "Default")
      (node (ref "U10") (pin "AB21") (pinfunction "IO_L69P_1_AB21") (pintype "passive+no_connect"))
    )
    (net (code "178") (name "unconnected-(U10B-IO_L70N_1-PadV20)") (class "Default")
      (node (ref "U10") (pin "V20") (pinfunction "IO_L70N_1_V20") (pintype "passive+no_connect"))
    )
    (net (code "179") (name "unconnected-(U10B-IO_L70P_1-PadU19)") (class "Default")
      (node (ref "U10") (pin "U19") (pinfunction "IO_L70P_1_U19") (pintype "passive+no_connect"))
    )
    (net (code "180") (name "unconnected-(U10B-IO_L71N_1-PadW22)") (class "Default")
      (node (ref "U10") (pin "W22") (pinfunction "IO_L71N_1_W22") (pintype "passive+no_connect"))
    )
    (net (code "181") (name "unconnected-(U10B-IO_L71P_1-PadV22)") (class "Default")
      (node (ref "U10") (pin "V22") (pinfunction "IO_L71P_1_V22") (pintype "passive+no_connect"))
    )
    (net (code "182") (name "unconnected-(U10B-IO_L72N_1-PadY21)") (class "Default")
      (node (ref "U10") (pin "Y21") (pinfunction "IO_L72N_1_Y21") (pintype "passive+no_connect"))
    )
    (net (code "183") (name "unconnected-(U10B-IO_L72P_1-PadY20)") (class "Default")
      (node (ref "U10") (pin "Y20") (pinfunction "IO_L72P_1_Y20") (pintype "passive+no_connect"))
    )
    (net (code "184") (name "unconnected-(U10B-IO_L73N_1-PadAA22)") (class "Default")
      (node (ref "U10") (pin "AA22") (pinfunction "IO_L73N_1_AA22") (pintype "passive+no_connect"))
    )
    (net (code "185") (name "unconnected-(U10B-IO_L73P_1-PadY22)") (class "Default")
      (node (ref "U10") (pin "Y22") (pinfunction "IO_L73P_1_Y22") (pintype "passive+no_connect"))
    )
    (net (code "186") (name "unconnected-(U10B-IO_L74N_DOUT_BUSY_1-PadAF24)") (class "Default")
      (node (ref "U10") (pin "AF24") (pinfunction "IO_L74N_DOUT_BUSY_1_AF24") (pintype "passive+no_connect"))
    )
    (net (code "187") (name "unconnected-(U10B-IO_L74P_AWAKE_1-PadAE23)") (class "Default")
      (node (ref "U10") (pin "AE23") (pinfunction "IO_L74P_AWAKE_1_AE23") (pintype "passive+no_connect"))
    )
  )
)
